# stwin_bluetooth_iNEMO.net
KiCad netlist of a schematic drawn in EAGLE
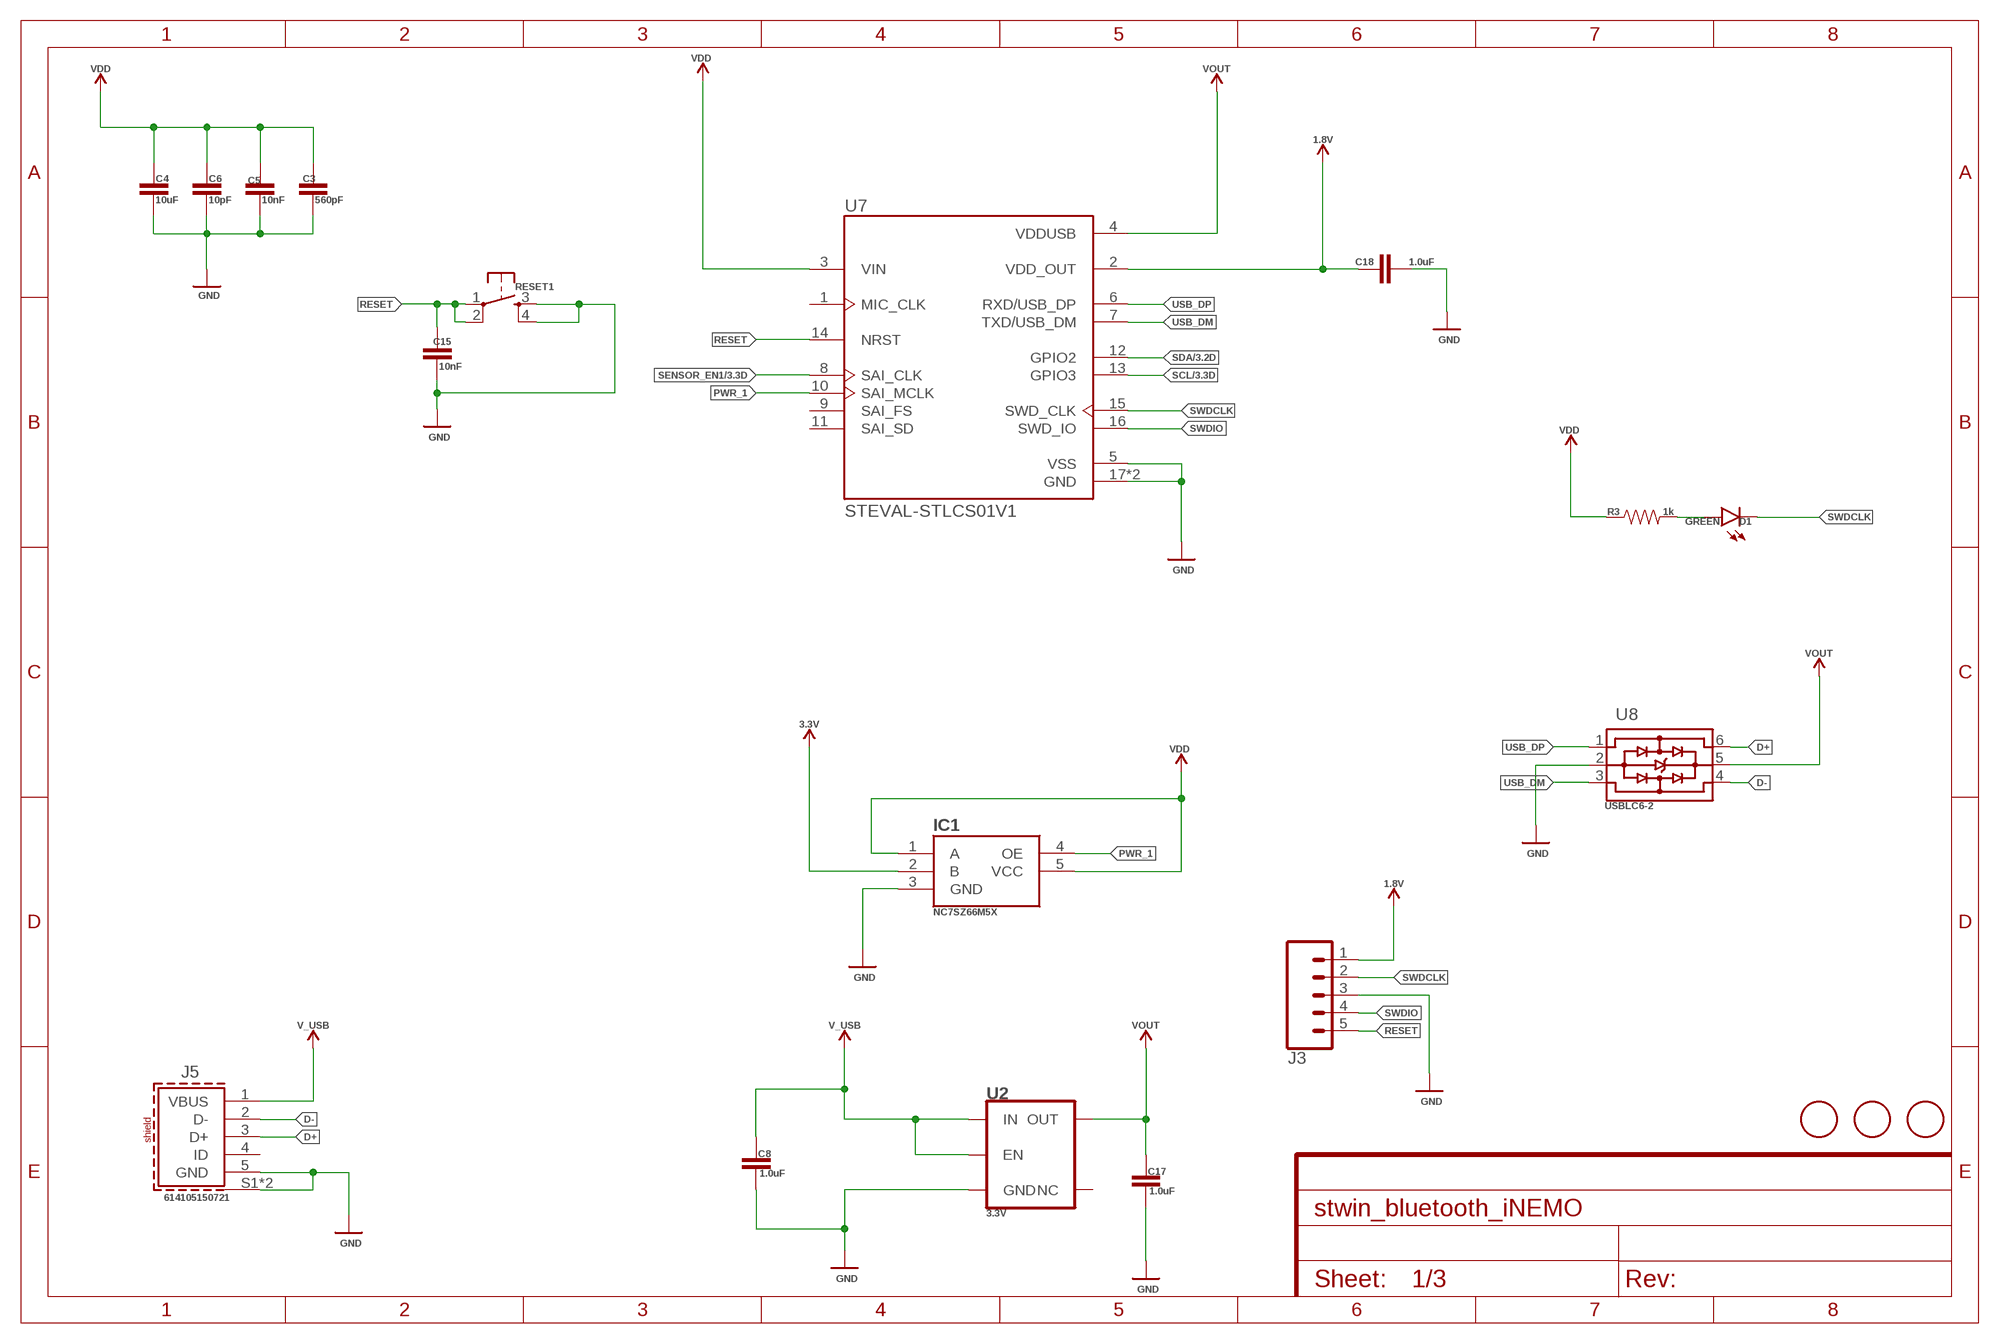
[diagram p0: schematic, sheet 1]
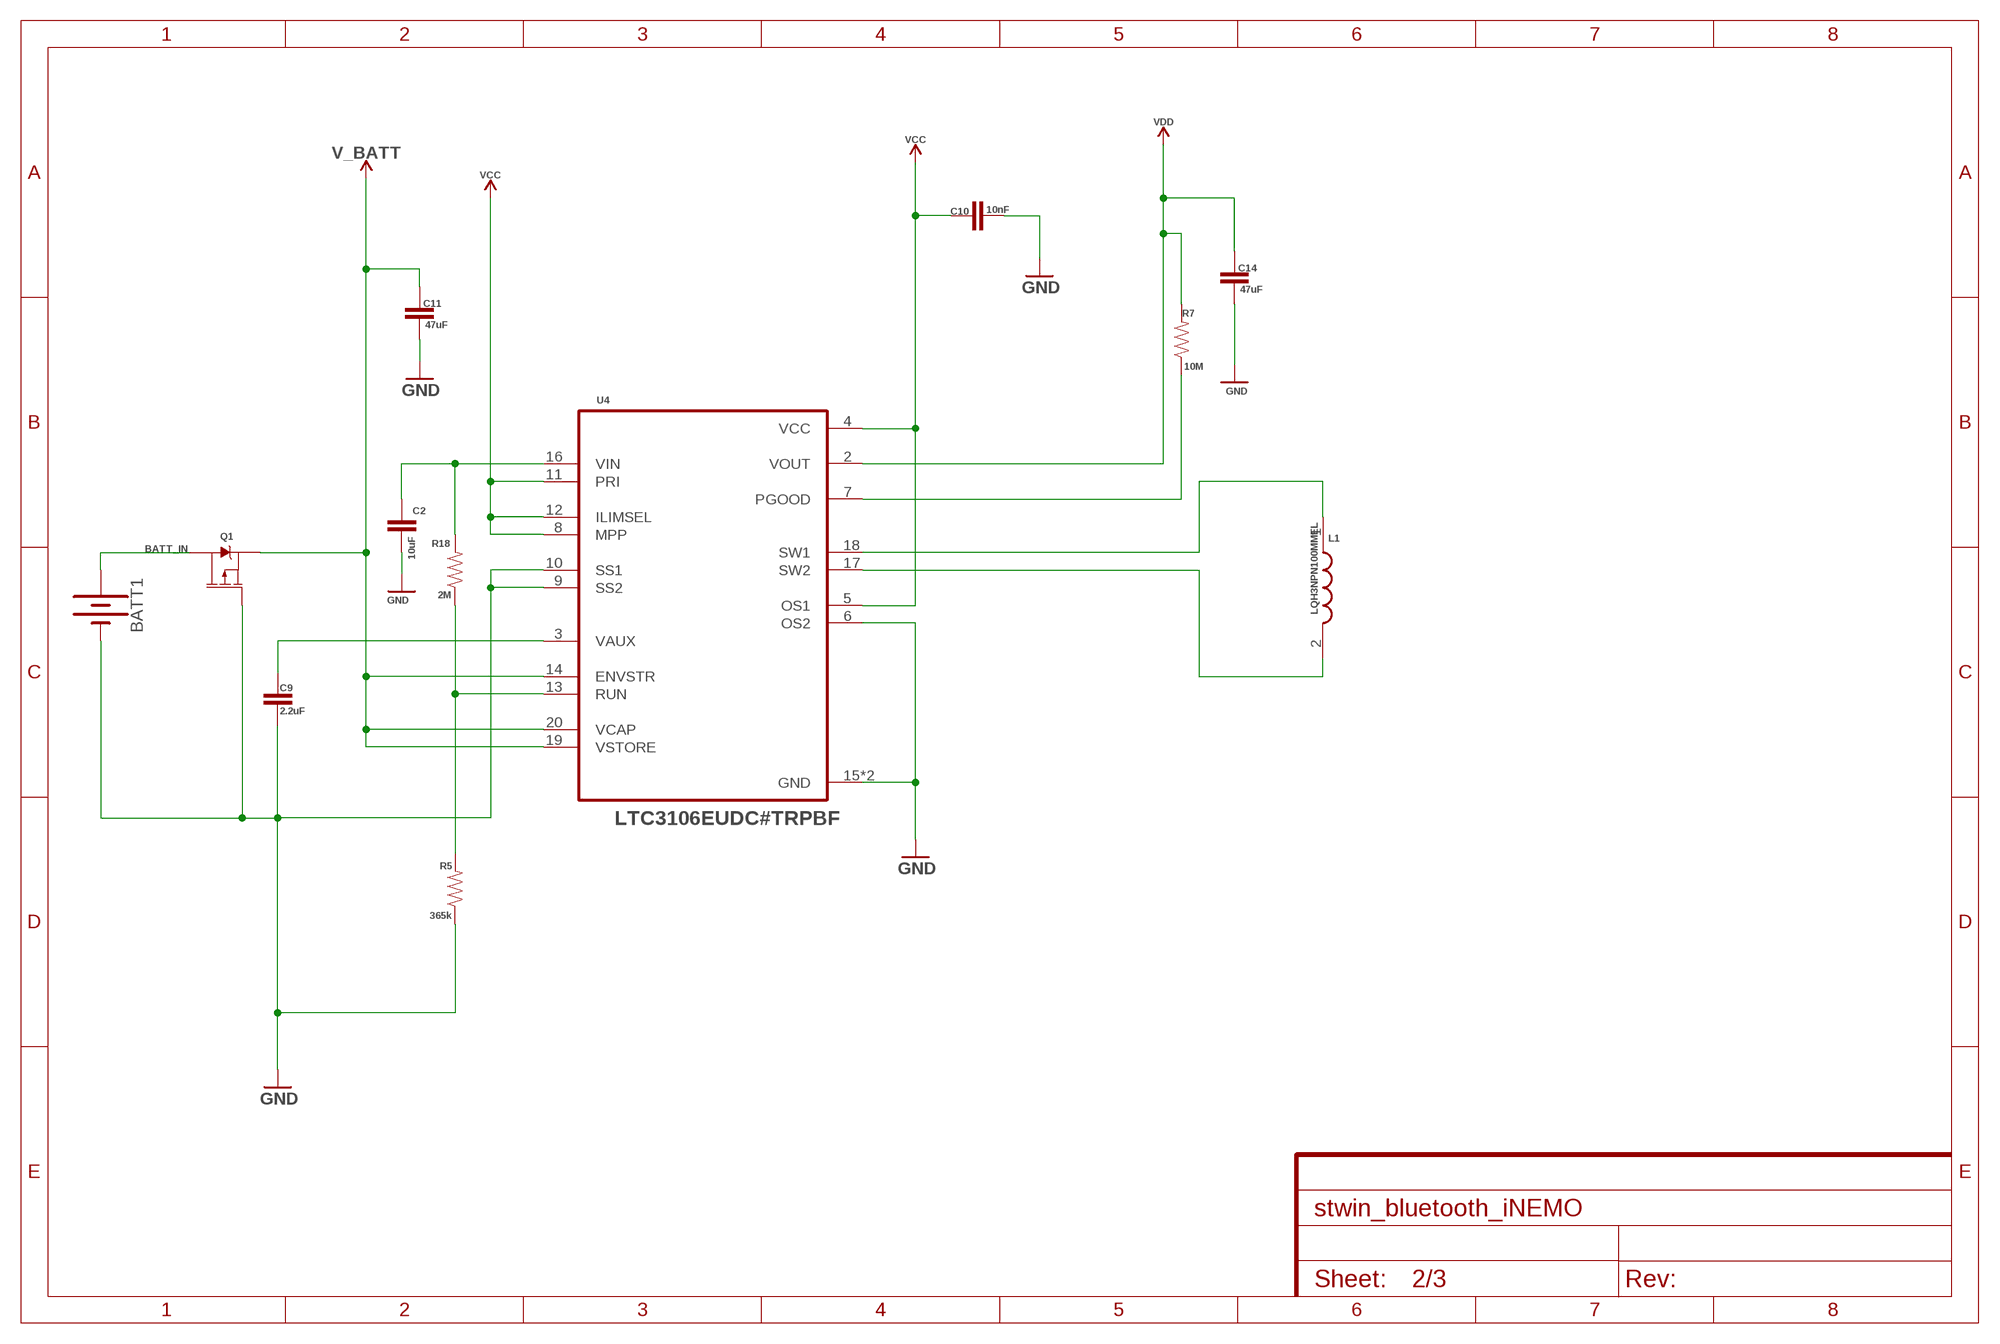
[diagram p1: schematic, sheet 2]
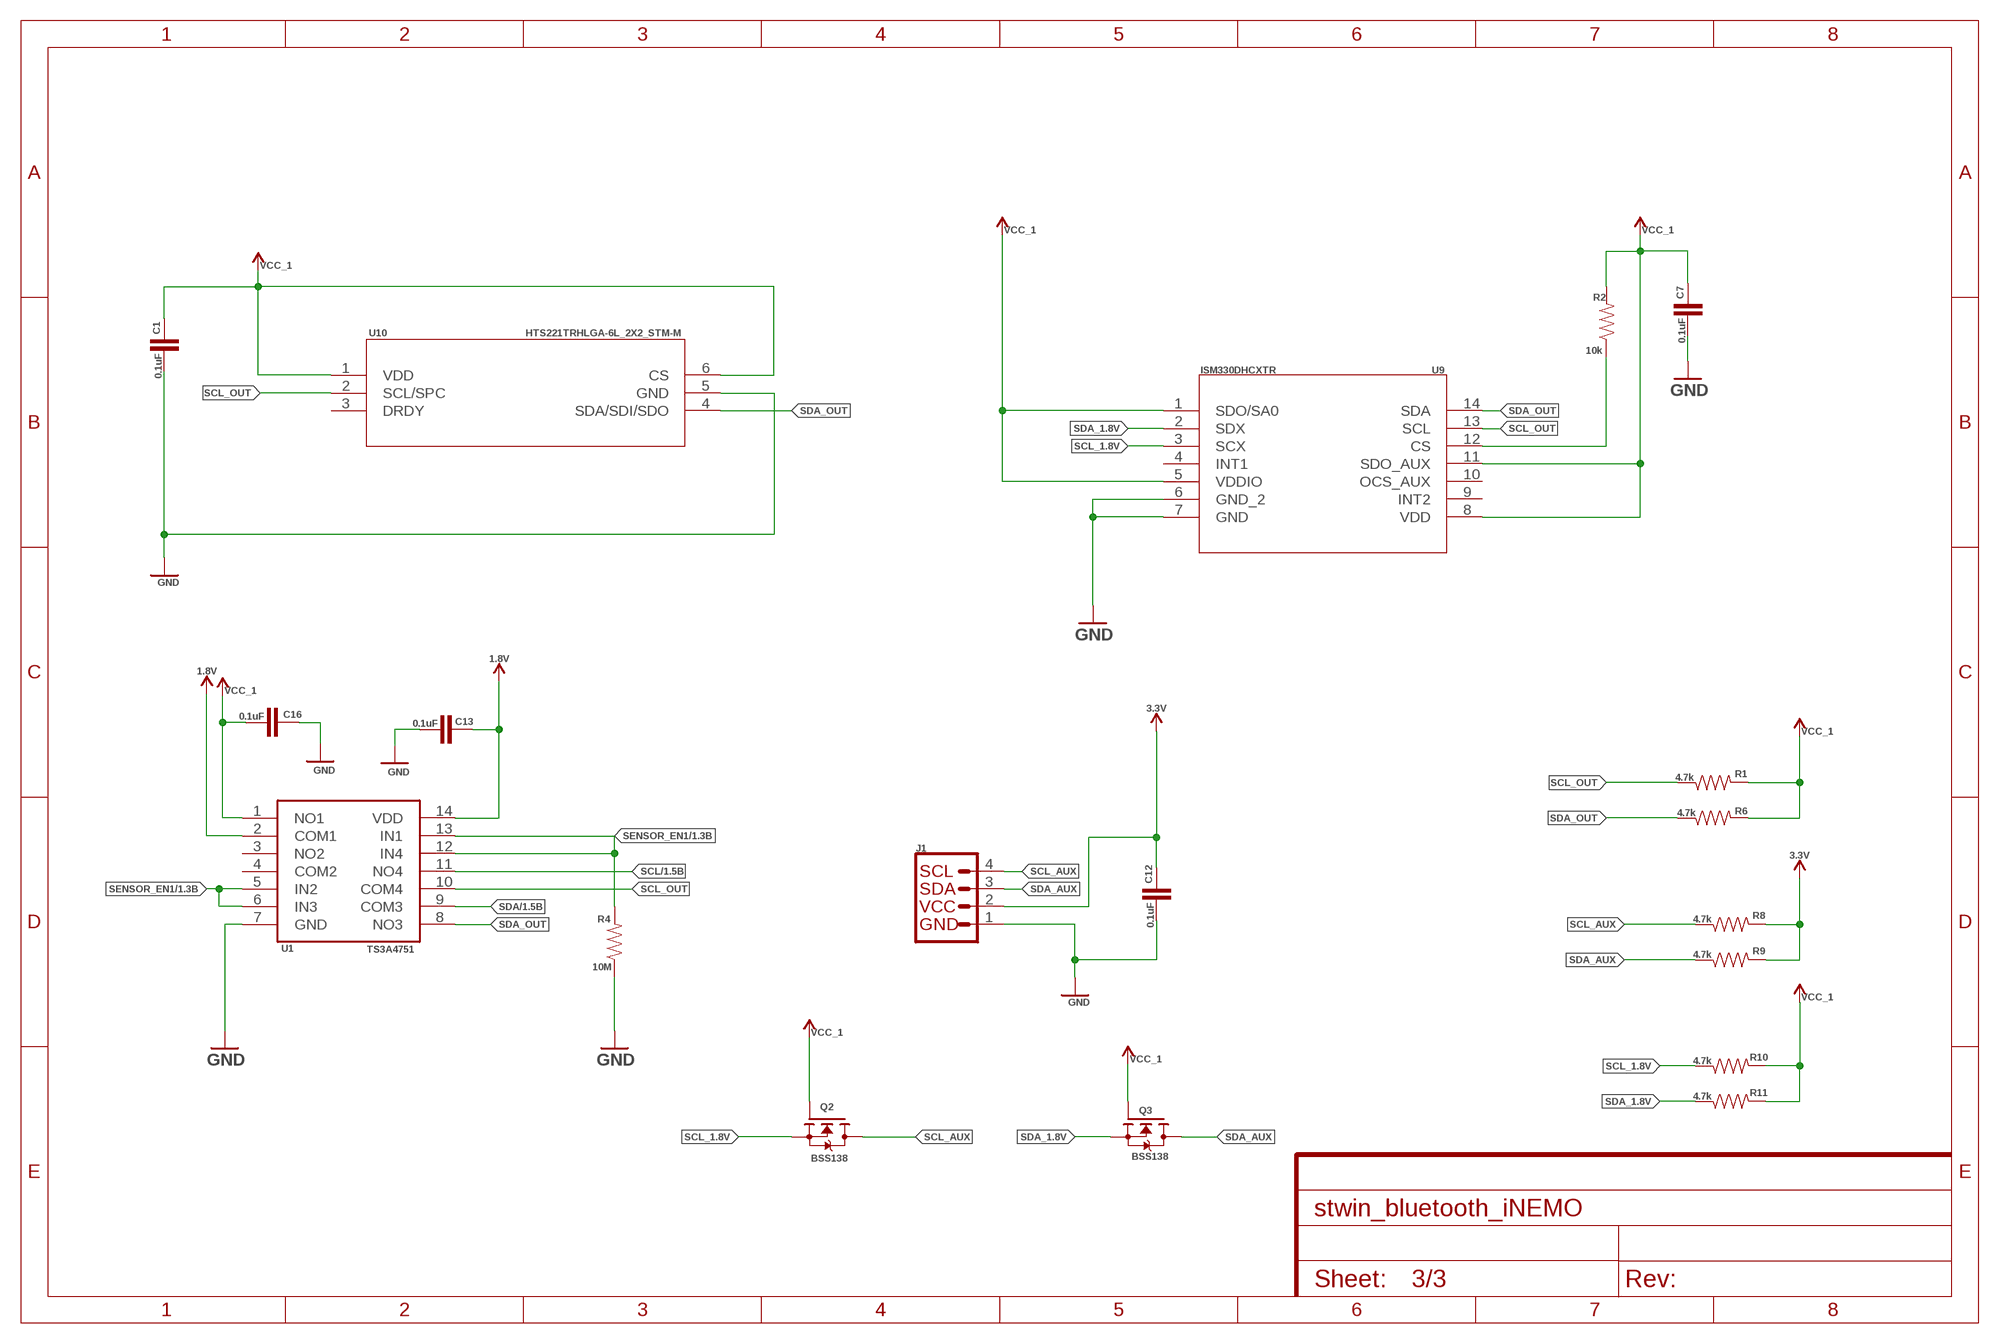
[diagram p2: schematic, sheet 3]

(export (version "E")
  (design (tool "Eeschema 10.0.6"))
  (components
    (comp (ref "C3")
      (value "560pF")
      (footprint "eagle-import:0603")
      (libsource (lib "eagle-import") (part "560PF-0603-50V-5%"))
    )
    (comp (ref "C4")
      (value "10uF")
      (footprint "eagle-import:0603")
      (libsource (lib "eagle-import") (part "10UF-0603-6.3V-20%"))
    )
    (comp (ref "C5")
      (value "10nF")
      (footprint "eagle-import:0603")
      (libsource (lib "eagle-import") (part "10NF-0603-50V-10%"))
    )
    (comp (ref "C6")
      (value "10pF")
      (footprint "eagle-import:0603")
      (libsource (lib "eagle-import") (part "10PF-0603-50V-5%"))
    )
    (comp (ref "C8")
      (value "1.0uF")
      (footprint "eagle-import:0603")
      (libsource (lib "eagle-import") (part "1.0UF-0603-16V-10%"))
    )
    (comp (ref "C15")
      (value "10nF")
      (footprint "eagle-import:0603")
      (libsource (lib "eagle-import") (part "10NF-0603-50V-10%"))
    )
    (comp (ref "C17")
      (value "1.0uF")
      (footprint "eagle-import:0603")
      (libsource (lib "eagle-import") (part "1.0UF-0603-16V-10%"))
    )
    (comp (ref "C18")
      (value "1.0uF")
      (footprint "eagle-import:0603")
      (libsource (lib "eagle-import") (part "1.0UF-0603-16V-10%"))
    )
    (comp (ref "D1")
      (value "GREEN")
      (footprint "eagle-import:LED-0603")
      (libsource (lib "eagle-import") (part "LED-GREEN0603"))
    )
    (comp (ref "IC1")
      (value "NC7SZ66M5X")
      (footprint "eagle-import:SOT95P280X145-5N")
      (fields (field (name "MOUSER_PART_NUMBER") "512-NC7SZ66M5X"))
      (libsource (lib "eagle-import") (part "NC7SZ66M5X"))
    )
    (comp (ref "J3")
      (value "CONN_05LOCK_LONGPADS")
      (footprint "eagle-import:1X05_LOCK_LONGPADS")
      (libsource (lib "eagle-import") (part "CONN_05LOCK_LONGPADS"))
    )
    (comp (ref "J5")
      (value "614105150721")
      (footprint "eagle-import:614105150721")
      (fields (field (name "MF") "Wurth Electronics"))
      (libsource (lib "eagle-import") (part "614105150721"))
    )
    (comp (ref "R3")
      (value "1k")
      (footprint "eagle-import:0603")
      (libsource (lib "eagle-import") (part "1KOHM-0603-1/10W-1%"))
    )
    (comp (ref "RESET1")
      (value "MOMENTARY-SWITCH-SPST-2-SMD-4.6X2.8MM")
      (footprint "eagle-import:TACTILE_SWITCH_SMD_4.6X2.8MM")
      (libsource (lib "eagle-import") (part "MOMENTARY-SWITCH-SPST-2-SMD-4.6X2.8MM"))
    )
    (comp (ref "U$5")
      (value "FIDUCIAL")
      (footprint "eagle-import:FIDUCIAL_1MM")
      (libsource (lib "eagle-import") (part "FIDUCIAL"))
    )
    (comp (ref "U$6")
      (value "FIDUCIAL")
      (footprint "eagle-import:FIDUCIAL_1MM")
      (libsource (lib "eagle-import") (part "FIDUCIAL"))
    )
    (comp (ref "U$7")
      (value "FIDUCIAL")
      (footprint "eagle-import:FIDUCIAL_1MM")
      (libsource (lib "eagle-import") (part "FIDUCIAL"))
    )
    (comp (ref "U2")
      (value "3.3V")
      (footprint "eagle-import:SOT23-5")
      (libsource (lib "eagle-import") (part "V_REG_AP2112K-3.3V"))
    )
    (comp (ref "U7")
      (value "STEVAL-STLCS01V1")
      (footprint "eagle-import:XDCR_STEVAL-STLCS01V1")
      (fields (field (name "MF") "STMicroelectronics"))
      (libsource (lib "eagle-import") (part "STEVAL-STLCS01V1"))
    )
    (comp (ref "U8")
      (value "USBLC6-2")
      (footprint "eagle-import:USBLC6-2P6")
      (fields (field (name "MF") "STMicroelectronics"))
      (libsource (lib "eagle-import") (part "USBLC6-2"))
    )
    (comp (ref "C1")
      (value "0.1uF")
      (footprint "eagle-import:0603")
      (libsource (lib "eagle-import") (part "0.1UF-0603-25V-(+80/-20%)"))
    )
    (comp (ref "C7")
      (value "0.1uF")
      (footprint "eagle-import:0603")
      (libsource (lib "eagle-import") (part "0.1UF-0603-25V-(+80/-20%)"))
    )
    (comp (ref "C12")
      (value "0.1uF")
      (footprint "eagle-import:0603")
      (libsource (lib "eagle-import") (part "0.1UF-0603-25V-(+80/-20%)"))
    )
    (comp (ref "C13")
      (value "0.1uF")
      (footprint "eagle-import:0603")
      (libsource (lib "eagle-import") (part "0.1UF-0603-25V-(+80/-20%)"))
    )
    (comp (ref "C16")
      (value "0.1uF")
      (footprint "eagle-import:0603")
      (libsource (lib "eagle-import") (part "0.1UF-0603-25V-(+80/-20%)"))
    )
    (comp (ref "J1")
      (value "I2C_STANDARD")
      (footprint "eagle-import:1X04")
      (libsource (lib "eagle-import") (part "I2C_STANDARD"))
    )
    (comp (ref "Q2")
      (value "BSS138")
      (footprint "eagle-import:SOT95P240X111-3N")
      (fields (field (name "MF") "ON Semiconductor"))
      (libsource (lib "eagle-import") (part "BSS138"))
    )
    (comp (ref "Q3")
      (value "BSS138")
      (footprint "eagle-import:SOT95P240X111-3N")
      (fields (field (name "MF") "ON Semiconductor"))
      (libsource (lib "eagle-import") (part "BSS138"))
    )
    (comp (ref "R1")
      (value "4.7k")
      (footprint "eagle-import:0603")
      (libsource (lib "eagle-import") (part "4.7KOHM-0603-1/10W-1%"))
    )
    (comp (ref "R2")
      (value "10k")
      (footprint "eagle-import:0603")
      (libsource (lib "eagle-import") (part "10KOHM-0603-1/10W-1%"))
    )
    (comp (ref "R4")
      (value "10M")
      (footprint "eagle-import:0603")
      (libsource (lib "eagle-import") (part "10MOHM-0603-1/10W-5%"))
    )
    (comp (ref "R6")
      (value "4.7k")
      (footprint "eagle-import:0603")
      (libsource (lib "eagle-import") (part "4.7KOHM-0603-1/10W-1%"))
    )
    (comp (ref "R8")
      (value "4.7k")
      (footprint "eagle-import:0603")
      (libsource (lib "eagle-import") (part "4.7KOHM-0603-1/10W-1%"))
    )
    (comp (ref "R9")
      (value "4.7k")
      (footprint "eagle-import:0603")
      (libsource (lib "eagle-import") (part "4.7KOHM-0603-1/10W-1%"))
    )
    (comp (ref "R10")
      (value "4.7k")
      (footprint "eagle-import:0603")
      (libsource (lib "eagle-import") (part "4.7KOHM-0603-1/10W-1%"))
    )
    (comp (ref "R11")
      (value "4.7k")
      (footprint "eagle-import:0603")
      (libsource (lib "eagle-import") (part "4.7KOHM-0603-1/10W-1%"))
    )
    (comp (ref "U1")
      (value "TS3A4751")
      (footprint "eagle-import:14_PIN")
      (fields (field (name "MF") "Texas Instruments"))
      (libsource (lib "eagle-import") (part "TS3A4751"))
    )
    (comp (ref "U9")
      (value "ISM330DHCXTR")
      (footprint "eagle-import:QFN_DHCXTR_STM")
      (fields (field (name "COPYRIGHT") "Copyright (C) 2018 Accelerated Designs. All rights reserved"))
      (libsource (lib "eagle-import") (part "ISM330DHCXTR"))
    )
    (comp (ref "U10")
      (value "HTS221TRHLGA-6L_2X2_STM-M")
      (footprint "eagle-import:HLGA-6L_2X2_STM-M")
      (fields
        (field (name "MANUFACTURER_PART_NUMBER") "HTS221TR")
        (field (name "COPYRIGHT") "Copyright (C) 2018 Accelerated Designs. All rights reserved")
      )
      (libsource (lib "eagle-import") (part "HTS221TRHLGA-6L_2X2_STM-M"))
    )
    (comp (ref "BATT1")
      (value "KEYSTONE_54KEYSTONE_2")
      (footprint "eagle-import:KEYSTONE_V2")
      (libsource (lib "eagle-import") (part "KEYSTONE_54KEYSTONE_2"))
    )
    (comp (ref "C2")
      (value "10uF")
      (footprint "eagle-import:0603")
      (libsource (lib "eagle-import") (part "10UF-0603-6.3V-20%"))
    )
    (comp (ref "C9")
      (value "2.2uF")
      (footprint "eagle-import:0603")
      (libsource (lib "eagle-import") (part "2.2UF-0603-10V-20%"))
    )
    (comp (ref "C10")
      (value "10nF")
      (footprint "eagle-import:0603")
      (libsource (lib "eagle-import") (part "10NF-0603-50V-10%"))
    )
    (comp (ref "C11")
      (value "47uF")
      (footprint "eagle-import:0603")
      (libsource (lib "eagle-import") (part "4.7UF0603"))
    )
    (comp (ref "C14")
      (value "47uF")
      (footprint "eagle-import:0603")
      (libsource (lib "eagle-import") (part "4.7UF0603"))
    )
    (comp (ref "L1")
      (value "LQH3NPN100MMEL")
      (footprint "eagle-import:INDPM3030X150N")
      (fields (field (name "MOUSER_PART_NUMBER") "81-LQH3NPN100MMEL"))
      (libsource (lib "eagle-import") (part "LQH3NPN100MMEL"))
    )
    (comp (ref "Q1")
      (value "2.5A/30V/105mΩ")
      (footprint "eagle-import:SOT23-3")
      (libsource (lib "eagle-import") (part "MOSFET_PCH-DMG2307L"))
    )
    (comp (ref "R5")
      (value "365k")
      (footprint "eagle-import:0603")
      (libsource (lib "eagle-import") (part "348KOHM-0603-1/10W-1%"))
    )
    (comp (ref "R7")
      (value "10M")
      (footprint "eagle-import:0603")
      (libsource (lib "eagle-import") (part "10MOHM-0603-1/10W-5%"))
    )
    (comp (ref "R18")
      (value "2M")
      (footprint "eagle-import:0603")
      (libsource (lib "eagle-import") (part "1MOHM-0603-1/4W-5%"))
    )
    (comp (ref "U4")
      (value "LTC3106EUDC#TRPBF")
      (footprint "eagle-import:QFN50P400X300X80-21N")
      (fields (field (name "MF") "Linear Technology/Analog"))
      (libsource (lib "eagle-import") (part "LTC3106EUDC#TRPBF"))
    )
  )
  (nets
    (net (code "1") (name "1.8V") (class "Default")
      (node (ref "C13") (pin "1") (pinfunction "1_1") (pintype "passive"))
      (node (ref "C18") (pin "1") (pinfunction "1_1") (pintype "passive"))
      (node (ref "J3") (pin "1") (pinfunction "1_1") (pintype "passive"))
      (node (ref "U1") (pin "14") (pinfunction "VDD_14") (pintype "bidirectional"))
      (node (ref "U1") (pin "2") (pinfunction "COM1_2") (pintype "bidirectional"))
      (node (ref "U7") (pin "2") (pinfunction "VDD_OUT_2") (pintype "output"))
    )
    (net (code "2") (name "3.3V") (class "Default")
      (node (ref "C12") (pin "1") (pinfunction "1_1") (pintype "passive"))
      (node (ref "IC1") (pin "2") (pinfunction "B_2") (pintype "bidirectional"))
      (node (ref "J1") (pin "2") (pinfunction "2_2") (pintype "power_in"))
      (node (ref "R8") (pin "2") (pinfunction "2_2") (pintype "passive"))
      (node (ref "R9") (pin "2") (pinfunction "2_2") (pintype "passive"))
    )
    (net (code "3") (name "BATT_IN") (class "Default")
      (node (ref "BATT1") (pin "P$1") (pinfunction "+_P$1") (pintype "power_in"))
      (node (ref "BATT1") (pin "P$2") (pinfunction "+_P$2") (pintype "power_in"))
      (node (ref "BATT1") (pin "P$3") (pinfunction "+_P$3") (pintype "power_in"))
      (node (ref "Q1") (pin "3") (pinfunction "D_3") (pintype "bidirectional"))
    )
    (net (code "4") (name "D+") (class "Default")
      (node (ref "J5") (pin "3") (pinfunction "D+_3") (pintype "passive"))
      (node (ref "U8") (pin "6") (pinfunction "6_6") (pintype "bidirectional"))
    )
    (net (code "5") (name "D-") (class "Default")
      (node (ref "J5") (pin "2") (pinfunction "D-_2") (pintype "passive"))
      (node (ref "U8") (pin "4") (pinfunction "4_4") (pintype "bidirectional"))
    )
    (net (code "6") (name "GND") (class "Default")
      (node (ref "BATT1") (pin "P$4") (pinfunction "-_P$4") (pintype "power_in"))
      (node (ref "BATT1") (pin "P$5") (pinfunction "-_P$5") (pintype "power_in"))
      (node (ref "BATT1") (pin "P$6") (pinfunction "-_P$6") (pintype "power_in"))
      (node (ref "C1") (pin "2") (pinfunction "2_2") (pintype "passive"))
      (node (ref "C10") (pin "2") (pinfunction "2_2") (pintype "passive"))
      (node (ref "C11") (pin "2") (pinfunction "2_2") (pintype "passive"))
      (node (ref "C12") (pin "2") (pinfunction "2_2") (pintype "passive"))
      (node (ref "C13") (pin "2") (pinfunction "2_2") (pintype "passive"))
      (node (ref "C14") (pin "2") (pinfunction "2_2") (pintype "passive"))
      (node (ref "C15") (pin "1") (pinfunction "1_1") (pintype "passive"))
      (node (ref "C16") (pin "1") (pinfunction "1_1") (pintype "passive"))
      (node (ref "C17") (pin "2") (pinfunction "2_2") (pintype "passive"))
      (node (ref "C18") (pin "2") (pinfunction "2_2") (pintype "passive"))
      (node (ref "C2") (pin "2") (pinfunction "2_2") (pintype "passive"))
      (node (ref "C3") (pin "1") (pinfunction "1_1") (pintype "passive"))
      (node (ref "C4") (pin "1") (pinfunction "1_1") (pintype "passive"))
      (node (ref "C5") (pin "1") (pinfunction "1_1") (pintype "passive"))
      (node (ref "C6") (pin "1") (pinfunction "1_1") (pintype "passive"))
      (node (ref "C7") (pin "2") (pinfunction "2_2") (pintype "passive"))
      (node (ref "C8") (pin "2") (pinfunction "2_2") (pintype "passive"))
      (node (ref "C9") (pin "2") (pinfunction "2_2") (pintype "passive"))
      (node (ref "IC1") (pin "3") (pinfunction "GND_3") (pintype "power_in"))
      (node (ref "J1") (pin "1") (pinfunction "1_1") (pintype "power_in"))
      (node (ref "J3") (pin "3") (pinfunction "3_3") (pintype "passive"))
      (node (ref "J5") (pin "5") (pinfunction "GND_5") (pintype "passive"))
      (node (ref "J5") (pin "S1") (pinfunction "SHIELD_S1") (pintype "passive"))
      (node (ref "J5") (pin "S2") (pinfunction "SHIELD_S2") (pintype "passive"))
      (node (ref "Q1") (pin "1") (pinfunction "G_1") (pintype "bidirectional"))
      (node (ref "R4") (pin "1") (pinfunction "1_1") (pintype "passive"))
      (node (ref "R5") (pin "1") (pinfunction "1_1") (pintype "passive"))
      (node (ref "RESET1") (pin "3") (pinfunction "3_3") (pintype "passive"))
      (node (ref "RESET1") (pin "4") (pinfunction "4_4") (pintype "passive"))
      (node (ref "U1") (pin "7") (pinfunction "GND_7") (pintype "bidirectional"))
      (node (ref "U10") (pin "5") (pinfunction "GND_5") (pintype "passive"))
      (node (ref "U2") (pin "2") (pinfunction "GND_2") (pintype "input"))
      (node (ref "U4") (pin "10") (pinfunction "SS1_10") (pintype "input"))
      (node (ref "U4") (pin "15") (pinfunction "GND_15") (pintype "power_in"))
      (node (ref "U4") (pin "21") (pinfunction "GND_21") (pintype "power_in"))
      (node (ref "U4") (pin "6") (pinfunction "OS2_6") (pintype "input"))
      (node (ref "U4") (pin "9") (pinfunction "SS2_9") (pintype "input"))
      (node (ref "U7") (pin "17") (pinfunction "GND_17") (pintype "power_in"))
      (node (ref "U7") (pin "18") (pinfunction "GND_18") (pintype "power_in"))
      (node (ref "U7") (pin "5") (pinfunction "VSS_5") (pintype "power_in"))
      (node (ref "U8") (pin "2") (pinfunction "2_2") (pintype "power_in"))
      (node (ref "U9") (pin "6") (pinfunction "GND_2_6") (pintype "passive"))
      (node (ref "U9") (pin "7") (pinfunction "GND_7") (pintype "passive"))
    )
    (net (code "7") (name "Net-(D1-PadA)") (class "Default")
      (node (ref "D1") (pin "A") (pinfunction "A_A") (pintype "passive"))
      (node (ref "R3") (pin "2") (pinfunction "2_2") (pintype "passive"))
    )
    (net (code "8") (name "Net-(U4-PGOOD)") (class "Default")
      (node (ref "R7") (pin "1") (pinfunction "1_1") (pintype "passive"))
      (node (ref "U4") (pin "7") (pinfunction "PGOOD_7") (pintype "bidirectional"))
    )
    (net (code "9") (name "Net-(U4-RUN)") (class "Default")
      (node (ref "R18") (pin "1") (pinfunction "1_1") (pintype "passive"))
      (node (ref "R5") (pin "2") (pinfunction "2_2") (pintype "passive"))
      (node (ref "U4") (pin "13") (pinfunction "RUN_13") (pintype "input"))
    )
    (net (code "10") (name "Net-(U4-SW1)") (class "Default")
      (node (ref "L1") (pin "1") (pinfunction "1_1") (pintype "bidirectional"))
      (node (ref "U4") (pin "18") (pinfunction "SW1_18") (pintype "bidirectional"))
    )
    (net (code "11") (name "Net-(U4-SW2)") (class "Default")
      (node (ref "L1") (pin "2") (pinfunction "2_2") (pintype "bidirectional"))
      (node (ref "U4") (pin "17") (pinfunction "SW2_17") (pintype "bidirectional"))
    )
    (net (code "12") (name "Net-(U4-VAUX)") (class "Default")
      (node (ref "C9") (pin "1") (pinfunction "1_1") (pintype "passive"))
      (node (ref "U4") (pin "3") (pinfunction "VAUX_3") (pintype "bidirectional"))
    )
    (net (code "13") (name "Net-(U4-VIN)") (class "Default")
      (node (ref "C2") (pin "1") (pinfunction "1_1") (pintype "passive"))
      (node (ref "R18") (pin "2") (pinfunction "2_2") (pintype "passive"))
      (node (ref "U4") (pin "16") (pinfunction "VIN_16") (pintype "input"))
    )
    (net (code "14") (name "Net-(U9-CS)") (class "Default")
      (node (ref "R2") (pin "1") (pinfunction "1_1") (pintype "passive"))
      (node (ref "U9") (pin "12") (pinfunction "CS_12") (pintype "passive"))
    )
    (net (code "15") (name "PWR_1") (class "Default")
      (node (ref "IC1") (pin "4") (pinfunction "OE_4") (pintype "input"))
      (node (ref "U7") (pin "10") (pinfunction "SAI_MCLK_10") (pintype "bidirectional"))
    )
    (net (code "16") (name "RESET") (class "Default")
      (node (ref "C15") (pin "2") (pinfunction "2_2") (pintype "passive"))
      (node (ref "J3") (pin "5") (pinfunction "5_5") (pintype "passive"))
      (node (ref "RESET1") (pin "1") (pinfunction "1_1") (pintype "passive"))
      (node (ref "RESET1") (pin "2") (pinfunction "2_2") (pintype "passive"))
      (node (ref "U7") (pin "14") (pinfunction "NRST_14") (pintype "input"))
    )
    (net (code "17") (name "SCL") (class "Default")
      (node (ref "U1") (pin "11") (pinfunction "NO4_11") (pintype "bidirectional"))
      (node (ref "U7") (pin "13") (pinfunction "GPIO3_13") (pintype "bidirectional"))
    )
    (net (code "18") (name "SCL_1.8V") (class "Default")
      (node (ref "Q2") (pin "2") (pinfunction "S_2") (pintype "passive"))
      (node (ref "R10") (pin "1") (pinfunction "1_1") (pintype "passive"))
      (node (ref "U9") (pin "3") (pinfunction "SCX_3") (pintype "passive"))
    )
    (net (code "19") (name "SCL_AUX") (class "Default")
      (node (ref "J1") (pin "4") (pinfunction "4_4") (pintype "passive"))
      (node (ref "Q2") (pin "3") (pinfunction "D_3") (pintype "passive"))
      (node (ref "R8") (pin "1") (pinfunction "1_1") (pintype "passive"))
    )
    (net (code "20") (name "SCL_OUT") (class "Default")
      (node (ref "R1") (pin "1") (pinfunction "1_1") (pintype "passive"))
      (node (ref "U1") (pin "10") (pinfunction "COM4_10") (pintype "bidirectional"))
      (node (ref "U10") (pin "2") (pinfunction "SCL/SPC_2") (pintype "passive"))
      (node (ref "U9") (pin "13") (pinfunction "SCL_13") (pintype "passive"))
    )
    (net (code "21") (name "SDA") (class "Default")
      (node (ref "U1") (pin "9") (pinfunction "COM3_9") (pintype "bidirectional"))
      (node (ref "U7") (pin "12") (pinfunction "GPIO2_12") (pintype "bidirectional"))
    )
    (net (code "22") (name "SDA_1.8V") (class "Default")
      (node (ref "Q3") (pin "2") (pinfunction "S_2") (pintype "passive"))
      (node (ref "R11") (pin "1") (pinfunction "1_1") (pintype "passive"))
      (node (ref "U9") (pin "2") (pinfunction "SDX_2") (pintype "passive"))
    )
    (net (code "23") (name "SDA_AUX") (class "Default")
      (node (ref "J1") (pin "3") (pinfunction "3_3") (pintype "passive"))
      (node (ref "Q3") (pin "3") (pinfunction "D_3") (pintype "passive"))
      (node (ref "R9") (pin "1") (pinfunction "1_1") (pintype "passive"))
    )
    (net (code "24") (name "SDA_OUT") (class "Default")
      (node (ref "R6") (pin "1") (pinfunction "1_1") (pintype "passive"))
      (node (ref "U1") (pin "8") (pinfunction "NO3_8") (pintype "bidirectional"))
      (node (ref "U10") (pin "4") (pinfunction "SDA/SDI/SDO_4") (pintype "passive"))
      (node (ref "U9") (pin "14") (pinfunction "SDA_14") (pintype "passive"))
    )
    (net (code "25") (name "SENSOR_EN1") (class "Default")
      (node (ref "R4") (pin "2") (pinfunction "2_2") (pintype "passive"))
      (node (ref "U1") (pin "12") (pinfunction "IN4_12") (pintype "bidirectional"))
      (node (ref "U1") (pin "13") (pinfunction "IN1_13") (pintype "bidirectional"))
      (node (ref "U1") (pin "5") (pinfunction "IN2_5") (pintype "bidirectional"))
      (node (ref "U1") (pin "6") (pinfunction "IN3_6") (pintype "bidirectional"))
      (node (ref "U7") (pin "8") (pinfunction "SAI_CLK_8") (pintype "bidirectional"))
    )
    (net (code "26") (name "SWDCLK") (class "Default")
      (node (ref "D1") (pin "C") (pinfunction "C_C") (pintype "passive"))
      (node (ref "J3") (pin "2") (pinfunction "2_2") (pintype "passive"))
      (node (ref "U7") (pin "15") (pinfunction "SWD_CLK_15") (pintype "bidirectional"))
    )
    (net (code "27") (name "SWDIO") (class "Default")
      (node (ref "J3") (pin "4") (pinfunction "4_4") (pintype "passive"))
      (node (ref "U7") (pin "16") (pinfunction "SWD_IO_16") (pintype "bidirectional"))
    )
    (net (code "28") (name "USB_DM") (class "Default")
      (node (ref "U7") (pin "7") (pinfunction "TXD/USB_DM_7") (pintype "bidirectional"))
      (node (ref "U8") (pin "3") (pinfunction "3_3") (pintype "bidirectional"))
    )
    (net (code "29") (name "USB_DP") (class "Default")
      (node (ref "U7") (pin "6") (pinfunction "RXD/USB_DP_6") (pintype "bidirectional"))
      (node (ref "U8") (pin "1") (pinfunction "1_1") (pintype "bidirectional"))
    )
    (net (code "30") (name "VCC") (class "Default")
      (node (ref "C10") (pin "1") (pinfunction "1_1") (pintype "passive"))
      (node (ref "U4") (pin "11") (pinfunction "PRI_11") (pintype "input"))
      (node (ref "U4") (pin "12") (pinfunction "ILIMSEL_12") (pintype "input"))
      (node (ref "U4") (pin "4") (pinfunction "VCC_4") (pintype "power_in"))
      (node (ref "U4") (pin "5") (pinfunction "OS1_5") (pintype "input"))
      (node (ref "U4") (pin "8") (pinfunction "MPP_8") (pintype "input"))
    )
    (net (code "31") (name "VCC_1") (class "Default")
      (node (ref "C1") (pin "1") (pinfunction "1_1") (pintype "passive"))
      (node (ref "C16") (pin "2") (pinfunction "2_2") (pintype "passive"))
      (node (ref "C7") (pin "1") (pinfunction "1_1") (pintype "passive"))
      (node (ref "Q2") (pin "1") (pinfunction "G_1") (pintype "passive"))
      (node (ref "Q3") (pin "1") (pinfunction "G_1") (pintype "passive"))
      (node (ref "R1") (pin "2") (pinfunction "2_2") (pintype "passive"))
      (node (ref "R10") (pin "2") (pinfunction "2_2") (pintype "passive"))
      (node (ref "R11") (pin "2") (pinfunction "2_2") (pintype "passive"))
      (node (ref "R2") (pin "2") (pinfunction "2_2") (pintype "passive"))
      (node (ref "R6") (pin "2") (pinfunction "2_2") (pintype "passive"))
      (node (ref "U1") (pin "1") (pinfunction "NO1_1") (pintype "bidirectional"))
      (node (ref "U10") (pin "1") (pinfunction "VDD_1") (pintype "power_in"))
      (node (ref "U10") (pin "6") (pinfunction "CS_6") (pintype "passive"))
      (node (ref "U9") (pin "1") (pinfunction "SDO/SA0_1") (pintype "passive"))
      (node (ref "U9") (pin "11") (pinfunction "SDO_AUX_11") (pintype "passive"))
      (node (ref "U9") (pin "5") (pinfunction "VDDIO_5") (pintype "power_in"))
      (node (ref "U9") (pin "8") (pinfunction "VDD_8") (pintype "power_in"))
    )
    (net (code "32") (name "VDD") (class "Default")
      (node (ref "C14") (pin "1") (pinfunction "1_1") (pintype "passive"))
      (node (ref "C3") (pin "2") (pinfunction "2_2") (pintype "passive"))
      (node (ref "C4") (pin "2") (pinfunction "2_2") (pintype "passive"))
      (node (ref "C5") (pin "2") (pinfunction "2_2") (pintype "passive"))
      (node (ref "C6") (pin "2") (pinfunction "2_2") (pintype "passive"))
      (node (ref "IC1") (pin "1") (pinfunction "A_1") (pintype "bidirectional"))
      (node (ref "IC1") (pin "5") (pinfunction "VCC_5") (pintype "power_in"))
      (node (ref "R3") (pin "1") (pinfunction "1_1") (pintype "passive"))
      (node (ref "R7") (pin "2") (pinfunction "2_2") (pintype "passive"))
      (node (ref "U4") (pin "2") (pinfunction "VOUT_2") (pintype "output"))
      (node (ref "U7") (pin "3") (pinfunction "VIN_3") (pintype "input"))
    )
    (net (code "33") (name "VOUT") (class "Default")
      (node (ref "C17") (pin "1") (pinfunction "1_1") (pintype "passive"))
      (node (ref "U2") (pin "5") (pinfunction "OUT_5") (pintype "passive"))
      (node (ref "U7") (pin "4") (pinfunction "VDDUSB_4") (pintype "power_in"))
      (node (ref "U8") (pin "5") (pinfunction "5_5") (pintype "power_in"))
    )
    (net (code "34") (name "V_BATT") (class "Default")
      (node (ref "C11") (pin "1") (pinfunction "1_1") (pintype "passive"))
      (node (ref "Q1") (pin "2") (pinfunction "S_2") (pintype "bidirectional"))
      (node (ref "U4") (pin "14") (pinfunction "ENVSTR_14") (pintype "input"))
      (node (ref "U4") (pin "19") (pinfunction "VSTORE_19") (pintype "bidirectional"))
      (node (ref "U4") (pin "20") (pinfunction "VCAP_20") (pintype "bidirectional"))
    )
    (net (code "35") (name "V_USB") (class "Default")
      (node (ref "C8") (pin "1") (pinfunction "1_1") (pintype "passive"))
      (node (ref "J5") (pin "1") (pinfunction "VBUS_1") (pintype "passive"))
      (node (ref "U2") (pin "1") (pinfunction "IN_1") (pintype "input"))
      (node (ref "U2") (pin "3") (pinfunction "EN_3") (pintype "input"))
    )
    (net (code "36") (name "unconnected-(J5-ID-Pad4)") (class "Default")
      (node (ref "J5") (pin "4") (pinfunction "ID_4") (pintype "passive"))
    )
    (net (code "37") (name "unconnected-(U1-COM2-Pad4)") (class "Default")
      (node (ref "U1") (pin "4") (pinfunction "COM2_4") (pintype "bidirectional"))
    )
    (net (code "38") (name "unconnected-(U1-NO2-Pad3)") (class "Default")
      (node (ref "U1") (pin "3") (pinfunction "NO2_3") (pintype "bidirectional"))
    )
    (net (code "39") (name "unconnected-(U2-NC-Pad4)") (class "Default")
      (node (ref "U2") (pin "4") (pinfunction "NC_4") (pintype "no_connect"))
    )
    (net (code "40") (name "unconnected-(U7-MIC_CLK-Pad1)") (class "Default")
      (node (ref "U7") (pin "1") (pinfunction "MIC_CLK_1") (pintype "input"))
    )
    (net (code "41") (name "unconnected-(U7-SAI_FS-Pad9)") (class "Default")
      (node (ref "U7") (pin "9") (pinfunction "SAI_FS_9") (pintype "bidirectional"))
    )
    (net (code "42") (name "unconnected-(U7-SAI_SD-Pad11)") (class "Default")
      (node (ref "U7") (pin "11") (pinfunction "SAI_SD_11") (pintype "bidirectional"))
    )
    (net (code "43") (name "unconnected-(U9-INT1-Pad4)") (class "Default")
      (node (ref "U9") (pin "4") (pinfunction "INT1_4") (pintype "input"))
    )
    (net (code "44") (name "unconnected-(U9-INT2-Pad9)") (class "Default")
      (node (ref "U9") (pin "9") (pinfunction "INT2_9") (pintype "input"))
    )
    (net (code "45") (name "unconnected-(U9-OCS_AUX-Pad10)") (class "Default")
      (node (ref "U9") (pin "10") (pinfunction "OCS_AUX_10") (pintype "passive"))
    )
    (net (code "46") (name "unconnected-(U10-DRDY-Pad3)") (class "Default")
      (node (ref "U10") (pin "3") (pinfunction "DRDY_3") (pintype "passive"))
    )
  )
)
